# Microphone_Patch_Pedal.net
KiCad netlist of a schematic drawn in EAGLE
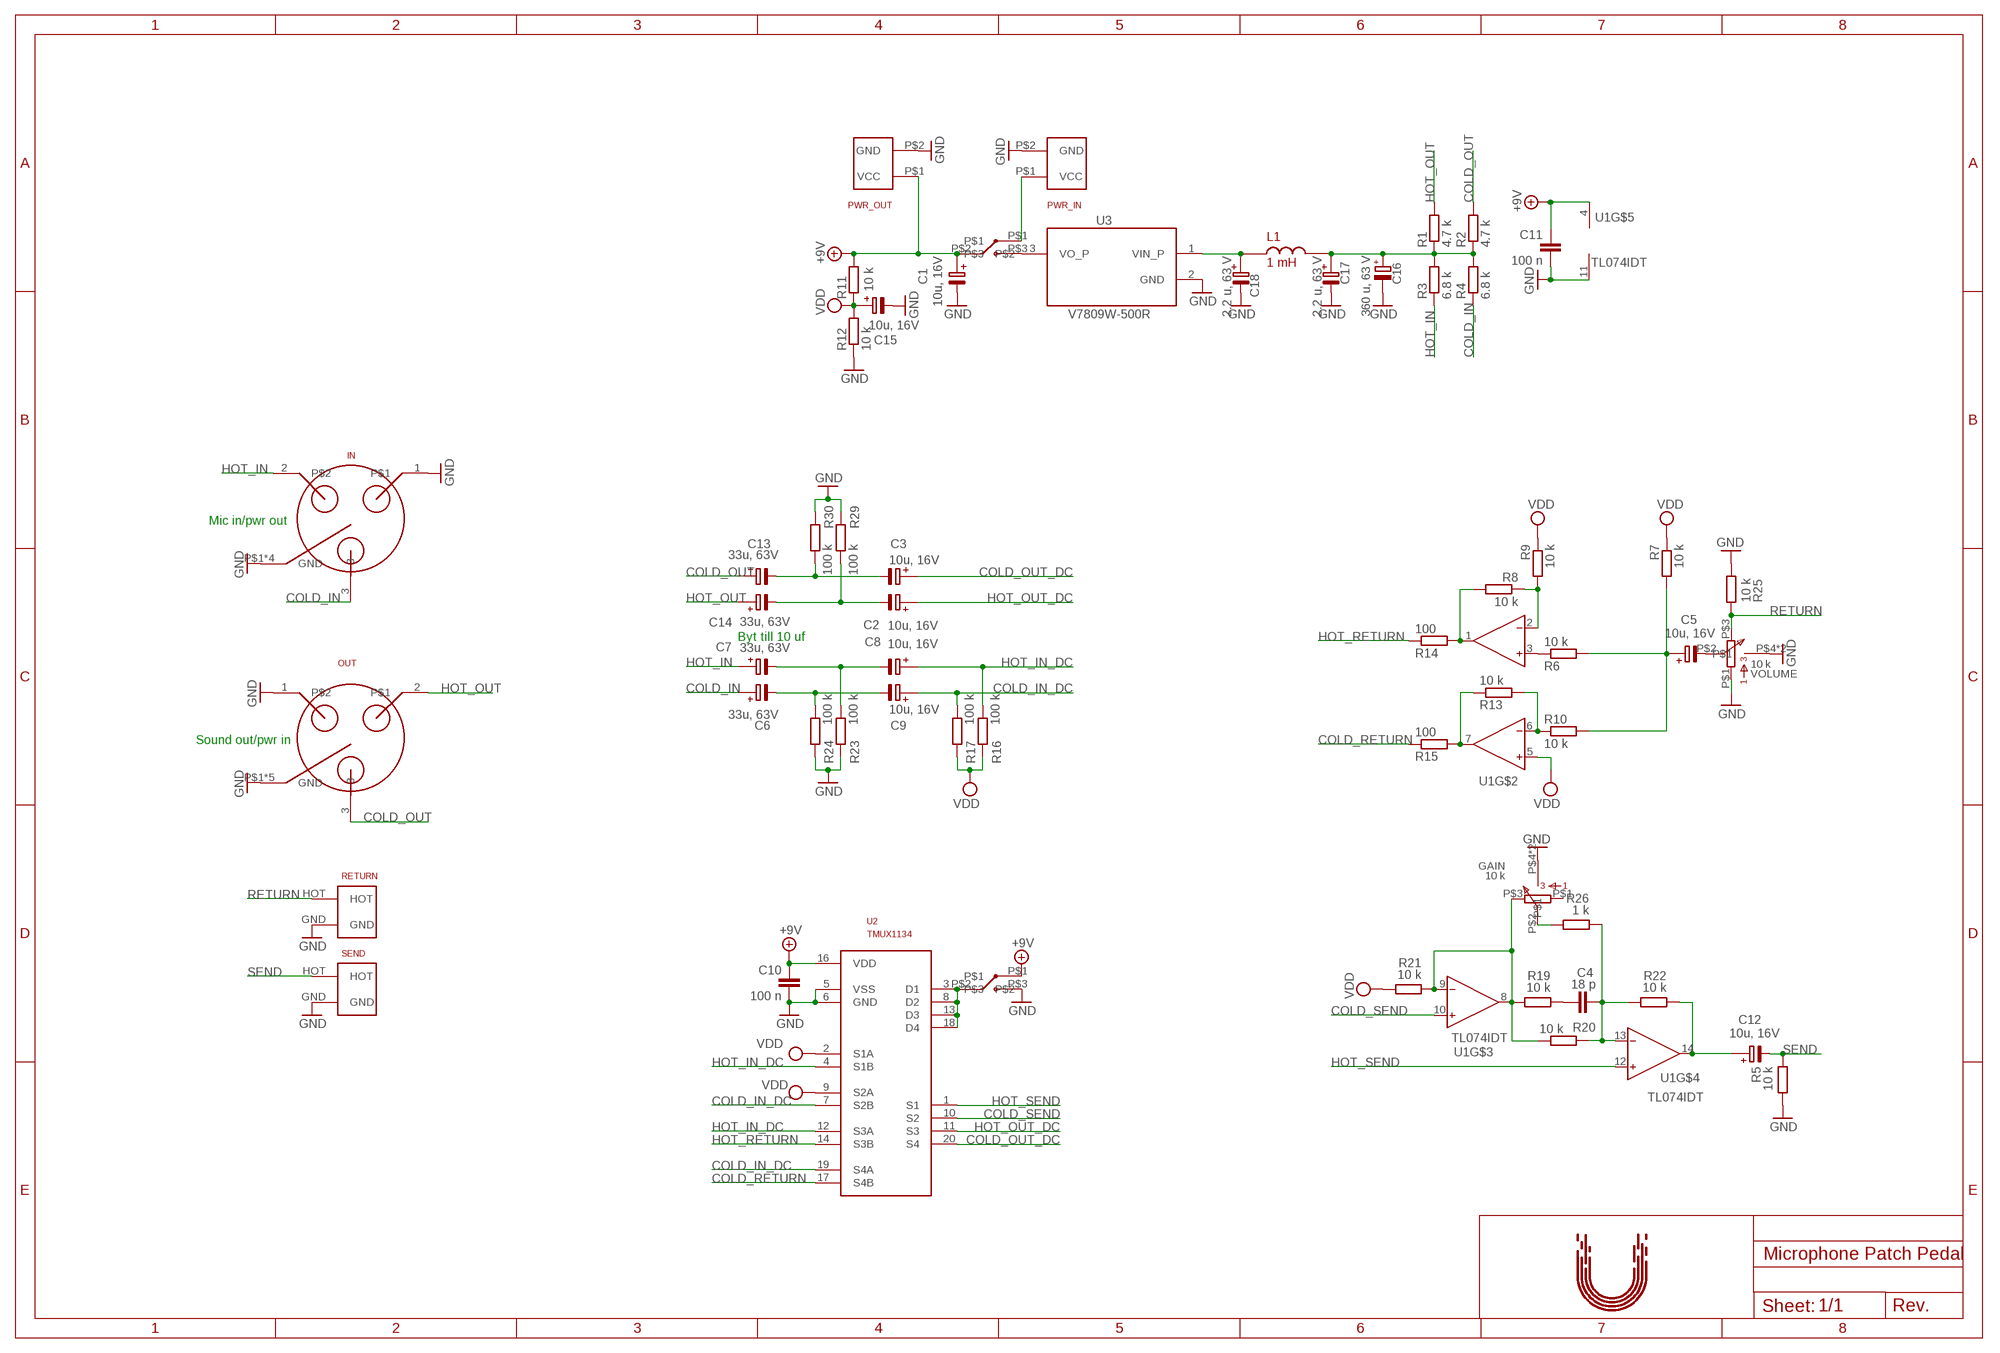
[diagram p0: schematic, sheet 1]

(export (version "E")
  (design (tool "Eeschema 10.0.6"))
  (components
    (comp (ref "BYPASS")
      (value "BUTTON")
      (footprint "eagle-import:3-HOLES")
      (libsource (lib "eagle-import") (part "BUTTON"))
    )
    (comp (ref "C1")
      (value "10u, 16V")
      (footprint "eagle-import:SV-A")
      (fields (field (name "MFR") "Nichicon"))
      (libsource (lib "eagle-import") (part "C-PR-SMD-SV-A"))
    )
    (comp (ref "C2")
      (value "10u, 16V")
      (footprint "eagle-import:SV-A")
      (fields (field (name "MFR") "Nichicon"))
      (libsource (lib "eagle-import") (part "C-PR-SMD-SV-A"))
    )
    (comp (ref "C3")
      (value "10u, 16V")
      (footprint "eagle-import:SV-A")
      (fields (field (name "MFR") "Nichicon"))
      (libsource (lib "eagle-import") (part "C-PR-SMD-SV-A"))
    )
    (comp (ref "C4")
      (value "18 p")
      (footprint "eagle-import:C0603")
      (libsource (lib "eagle-import") (part "C-EUC0603"))
    )
    (comp (ref "C5")
      (value "10u, 16V")
      (footprint "eagle-import:SV-A")
      (fields (field (name "MFR") "Nichicon"))
      (libsource (lib "eagle-import") (part "C-PR-SMD-SV-A"))
    )
    (comp (ref "C6")
      (value "33u, 63V")
      (footprint "eagle-import:SV-E_F")
      (fields (field (name "MFR") "Panasonic"))
      (libsource (lib "eagle-import") (part "C-PR-SMD-SV-E/F"))
    )
    (comp (ref "C7")
      (value "33u, 63V")
      (footprint "eagle-import:SV-E_F")
      (fields (field (name "MFR") "Panasonic"))
      (libsource (lib "eagle-import") (part "C-PR-SMD-SV-E/F"))
    )
    (comp (ref "C8")
      (value "10u, 16V")
      (footprint "eagle-import:SV-A")
      (fields (field (name "MFR") "Nichicon"))
      (libsource (lib "eagle-import") (part "C-PR-SMD-SV-A"))
    )
    (comp (ref "C9")
      (value "10u, 16V")
      (footprint "eagle-import:SV-A")
      (fields (field (name "MFR") "Nichicon"))
      (libsource (lib "eagle-import") (part "C-PR-SMD-SV-A"))
    )
    (comp (ref "C10")
      (value "100 n")
      (footprint "eagle-import:C0603")
      (libsource (lib "eagle-import") (part "C-EUC0603"))
    )
    (comp (ref "C11")
      (value "100 n")
      (footprint "eagle-import:C0603")
      (libsource (lib "eagle-import") (part "C-EUC0603"))
    )
    (comp (ref "C12")
      (value "10u, 16V")
      (footprint "eagle-import:SV-A")
      (fields (field (name "MFR") "Nichicon"))
      (libsource (lib "eagle-import") (part "C-PR-SMD-SV-A"))
    )
    (comp (ref "C13")
      (value "33u, 63V")
      (footprint "eagle-import:SV-E_F")
      (fields (field (name "MFR") "Panasonic"))
      (libsource (lib "eagle-import") (part "C-PR-SMD-SV-E/F"))
    )
    (comp (ref "C14")
      (value "33u, 63V")
      (footprint "eagle-import:SV-E_F")
      (fields (field (name "MFR") "Panasonic"))
      (libsource (lib "eagle-import") (part "C-PR-SMD-SV-E/F"))
    )
    (comp (ref "C15")
      (value "10u, 16V")
      (footprint "eagle-import:SV-A")
      (fields (field (name "MFR") "Nichicon"))
      (libsource (lib "eagle-import") (part "C-PR-SMD-SV-A"))
    )
    (comp (ref "C16")
      (value "360 u, 63 V")
      (footprint "eagle-import:PANASONIC_FK_V_H")
      (fields (field (name "MPN") "UCM1J361MNJ1MS"))
      (libsource (lib "eagle-import") (part "CPOL-EU-PANASONIC_FK_V_H"))
    )
    (comp (ref "C17")
      (value "2.2 u, 63 V")
      (footprint "eagle-import:SV-B")
      (fields (field (name "MPN") "EMVA630ADA2R2MD55G"))
      (libsource (lib "eagle-import") (part "C-PR-SMD-SV-B"))
    )
    (comp (ref "C18")
      (value "2.2 u, 63 V")
      (footprint "eagle-import:SV-B")
      (fields (field (name "MPN") "EMVA630ADA2R2MD55G"))
      (libsource (lib "eagle-import") (part "C-PR-SMD-SV-B"))
    )
    (comp (ref "GAIN")
      (value "10 k")
      (footprint "eagle-import:RK09L1140")
      (libsource (lib "eagle-import") (part "RK09L1140"))
    )
    (comp (ref "IN")
      (value "XLR_FEMALE")
      (footprint "eagle-import:NC3FAH2-S")
      (libsource (lib "eagle-import") (part "XLR_FEMALE"))
    )
    (comp (ref "L1")
      (value "1 mH")
      (footprint "eagle-import:R3225")
      (fields (field (name "MPN") "CBC3225T102KR"))
      (libsource (lib "eagle-import") (part "CBC3225T102KR"))
    )
    (comp (ref "OUT")
      (value "XLR_MALE")
      (footprint "eagle-import:NC3MAH-S")
      (libsource (lib "eagle-import") (part "XLR_MALE"))
    )
    (comp (ref "PWR_IN")
      (value "PWR")
      (footprint "eagle-import:PWR")
      (libsource (lib "eagle-import") (part "PWR"))
    )
    (comp (ref "PWR_OUT")
      (value "PWR")
      (footprint "eagle-import:PWR")
      (libsource (lib "eagle-import") (part "PWR"))
    )
    (comp (ref "R1")
      (value "4.7 k")
      (footprint "eagle-import:R0603")
      (libsource (lib "eagle-import") (part "R-EU_R0603"))
    )
    (comp (ref "R2")
      (value "4.7 k")
      (footprint "eagle-import:R0603")
      (libsource (lib "eagle-import") (part "R-EU_R0603"))
    )
    (comp (ref "R3")
      (value "6.8 k")
      (footprint "eagle-import:R0603")
      (libsource (lib "eagle-import") (part "R-EU_R0603"))
    )
    (comp (ref "R4")
      (value "6.8 k")
      (footprint "eagle-import:R0603")
      (libsource (lib "eagle-import") (part "R-EU_R0603"))
    )
    (comp (ref "R5")
      (value "10 k")
      (footprint "eagle-import:R0603")
      (libsource (lib "eagle-import") (part "R-EU_R0603"))
    )
    (comp (ref "R6")
      (value "10 k")
      (footprint "eagle-import:R0603")
      (libsource (lib "eagle-import") (part "R-EU_R0603"))
    )
    (comp (ref "R7")
      (value "10 k")
      (footprint "eagle-import:R0603")
      (libsource (lib "eagle-import") (part "R-EU_R0603"))
    )
    (comp (ref "R8")
      (value "10 k")
      (footprint "eagle-import:R0603")
      (libsource (lib "eagle-import") (part "R-EU_R0603"))
    )
    (comp (ref "R9")
      (value "10 k")
      (footprint "eagle-import:R0603")
      (libsource (lib "eagle-import") (part "R-EU_R0603"))
    )
    (comp (ref "R10")
      (value "10 k")
      (footprint "eagle-import:R0603")
      (libsource (lib "eagle-import") (part "R-EU_R0603"))
    )
    (comp (ref "R11")
      (value "10 k")
      (footprint "eagle-import:R0603")
      (libsource (lib "eagle-import") (part "R-EU_R0603"))
    )
    (comp (ref "R12")
      (value "10 k")
      (footprint "eagle-import:R0603")
      (libsource (lib "eagle-import") (part "R-EU_R0603"))
    )
    (comp (ref "R13")
      (value "10 k")
      (footprint "eagle-import:R0603")
      (libsource (lib "eagle-import") (part "R-EU_R0603"))
    )
    (comp (ref "R14")
      (value "100")
      (footprint "eagle-import:R0603")
      (libsource (lib "eagle-import") (part "R-EU_R0603"))
    )
    (comp (ref "R15")
      (value "100")
      (footprint "eagle-import:R0603")
      (libsource (lib "eagle-import") (part "R-EU_R0603"))
    )
    (comp (ref "R16")
      (value "100 k")
      (footprint "eagle-import:R0603")
      (libsource (lib "eagle-import") (part "R-EU_R0603"))
    )
    (comp (ref "R17")
      (value "100 k")
      (footprint "eagle-import:R0603")
      (libsource (lib "eagle-import") (part "R-EU_R0603"))
    )
    (comp (ref "R19")
      (value "10 k")
      (footprint "eagle-import:R0603")
      (libsource (lib "eagle-import") (part "R-EU_R0603"))
    )
    (comp (ref "R20")
      (value "10 k")
      (footprint "eagle-import:R0603")
      (libsource (lib "eagle-import") (part "R-EU_R0603"))
    )
    (comp (ref "R21")
      (value "10 k")
      (footprint "eagle-import:R0603")
      (libsource (lib "eagle-import") (part "R-EU_R0603"))
    )
    (comp (ref "R22")
      (value "10 k")
      (footprint "eagle-import:R0603")
      (libsource (lib "eagle-import") (part "R-EU_R0603"))
    )
    (comp (ref "R23")
      (value "100 k")
      (footprint "eagle-import:R0603")
      (libsource (lib "eagle-import") (part "R-EU_R0603"))
    )
    (comp (ref "R24")
      (value "100 k")
      (footprint "eagle-import:R0603")
      (libsource (lib "eagle-import") (part "R-EU_R0603"))
    )
    (comp (ref "R25")
      (value "10 k")
      (footprint "eagle-import:R0603")
      (libsource (lib "eagle-import") (part "R-EU_R0603"))
    )
    (comp (ref "R26")
      (value "1 k")
      (footprint "eagle-import:R0603")
      (libsource (lib "eagle-import") (part "R-EU_R0603"))
    )
    (comp (ref "R29")
      (value "100 k")
      (footprint "eagle-import:R0603")
      (libsource (lib "eagle-import") (part "R-EU_R0603"))
    )
    (comp (ref "R30")
      (value "100 k")
      (footprint "eagle-import:R0603")
      (libsource (lib "eagle-import") (part "R-EU_R0603"))
    )
    (comp (ref "RETURN")
      (value "UNBALANCED_INPUT_JACK")
      (footprint "eagle-import:BALANCED_INPUT_JACK")
      (libsource (lib "eagle-import") (part "UNBALANCED_INPUT_JACK"))
    )
    (comp (ref "SEND")
      (value "UNBALANCED_INPUT_JACK")
      (footprint "eagle-import:BALANCED_INPUT_JACK")
      (libsource (lib "eagle-import") (part "UNBALANCED_INPUT_JACK"))
    )
    (comp (ref "SWITCH")
      (value "BUTTON")
      (footprint "eagle-import:3-HOLES")
      (libsource (lib "eagle-import") (part "BUTTON"))
    )
    (comp (ref "U$1")
      (value "UTBULT_DESIGN4")
      (footprint "eagle-import:UD_4")
      (libsource (lib "eagle-import") (part "UTBULT_DESIGN4"))
    )
    (comp (ref "U1")
      (value "TL074IDT")
      (footprint "eagle-import:SOIC127P600X175-14N")
      (fields (field (name "MFR") "STMicroelectronics"))
      (libsource (lib "eagle-import") (part "TL074IDT"))
    )
    (comp (ref "U2")
      (value "TMUX1134")
      (footprint "eagle-import:SOP65P640X120-20N")
      (fields (field (name "MPN") "TMUX1134PWR "))
      (libsource (lib "eagle-import") (part "TMUX1134"))
    )
    (comp (ref "U3")
      (value "V7809W-500R")
      (footprint "eagle-import:CONV_V7809W-500R")
      (libsource (lib "eagle-import") (part "V7809W-500R"))
    )
    (comp (ref "VOLUME")
      (value "10 k")
      (footprint "eagle-import:RK09L1140")
      (libsource (lib "eagle-import") (part "RK09L1140"))
    )
  )
  (nets
    (net (code "1") (name "+9V") (class "Default")
      (node (ref "BYPASS") (pin "P$1") (pinfunction "P$1_P$1") (pintype "bidirectional"))
      (node (ref "C1") (pin "+") (pinfunction "+_+") (pintype "passive"))
      (node (ref "C10") (pin "1") (pinfunction "1_1") (pintype "passive"))
      (node (ref "C11") (pin "1") (pinfunction "1_1") (pintype "passive"))
      (node (ref "PWR_OUT") (pin "P$1") (pinfunction "VCC_P$1") (pintype "bidirectional"))
      (node (ref "R11") (pin "2") (pinfunction "2_2") (pintype "passive"))
      (node (ref "SWITCH") (pin "P$2") (pinfunction "P$2_P$2") (pintype "bidirectional"))
      (node (ref "U1") (pin "4") (pinfunction "V+_4") (pintype "power_in"))
      (node (ref "U2") (pin "16") (pinfunction "VDD_16") (pintype "bidirectional"))
    )
    (net (code "2") (name "/COLD_IN") (class "Default")
      (node (ref "C6") (pin "+") (pinfunction "+_+") (pintype "passive"))
      (node (ref "IN") (pin "3") (pinfunction "3_3") (pintype "bidirectional"))
      (node (ref "R4") (pin "1") (pinfunction "1_1") (pintype "passive"))
    )
    (net (code "3") (name "/COLD_IN_DC") (class "Default")
      (node (ref "C9") (pin "+") (pinfunction "+_+") (pintype "passive"))
      (node (ref "R17") (pin "2") (pinfunction "2_2") (pintype "passive"))
      (node (ref "U2") (pin "19") (pinfunction "S4A_19") (pintype "bidirectional"))
      (node (ref "U2") (pin "7") (pinfunction "S2B_7") (pintype "bidirectional"))
    )
    (net (code "4") (name "/COLD_OUT") (class "Default")
      (node (ref "C13") (pin "+") (pinfunction "+_+") (pintype "passive"))
      (node (ref "OUT") (pin "3") (pinfunction "3_3") (pintype "bidirectional"))
      (node (ref "R2") (pin "2") (pinfunction "2_2") (pintype "passive"))
    )
    (net (code "5") (name "/COLD_OUT_DC") (class "Default")
      (node (ref "C3") (pin "+") (pinfunction "+_+") (pintype "passive"))
      (node (ref "U2") (pin "20") (pinfunction "S4_20") (pintype "bidirectional"))
    )
    (net (code "6") (name "/COLD_RETURN") (class "Default")
      (node (ref "R15") (pin "1") (pinfunction "1_1") (pintype "passive"))
      (node (ref "U2") (pin "17") (pinfunction "S4B_17") (pintype "bidirectional"))
    )
    (net (code "7") (name "/COLD_SEND") (class "Default")
      (node (ref "U1") (pin "10") (pinfunction "IN+_10") (pintype "input"))
      (node (ref "U2") (pin "10") (pinfunction "S2_10") (pintype "bidirectional"))
    )
    (net (code "8") (name "/HOT_IN") (class "Default")
      (node (ref "C7") (pin "+") (pinfunction "+_+") (pintype "passive"))
      (node (ref "IN") (pin "2") (pinfunction "P$2_2") (pintype "bidirectional"))
      (node (ref "R3") (pin "1") (pinfunction "1_1") (pintype "passive"))
    )
    (net (code "9") (name "/HOT_IN_DC") (class "Default")
      (node (ref "C8") (pin "+") (pinfunction "+_+") (pintype "passive"))
      (node (ref "R16") (pin "2") (pinfunction "2_2") (pintype "passive"))
      (node (ref "U2") (pin "12") (pinfunction "S3A_12") (pintype "bidirectional"))
      (node (ref "U2") (pin "4") (pinfunction "S1B_4") (pintype "bidirectional"))
    )
    (net (code "10") (name "/HOT_OUT") (class "Default")
      (node (ref "C14") (pin "+") (pinfunction "+_+") (pintype "passive"))
      (node (ref "OUT") (pin "2") (pinfunction "P$1_2") (pintype "bidirectional"))
      (node (ref "R1") (pin "2") (pinfunction "2_2") (pintype "passive"))
    )
    (net (code "11") (name "/HOT_OUT_DC") (class "Default")
      (node (ref "C2") (pin "+") (pinfunction "+_+") (pintype "passive"))
      (node (ref "U2") (pin "11") (pinfunction "S3_11") (pintype "bidirectional"))
    )
    (net (code "12") (name "/HOT_RETURN") (class "Default")
      (node (ref "R14") (pin "1") (pinfunction "1_1") (pintype "passive"))
      (node (ref "U2") (pin "14") (pinfunction "S3B_14") (pintype "bidirectional"))
    )
    (net (code "13") (name "/HOT_SEND") (class "Default")
      (node (ref "U1") (pin "12") (pinfunction "IN+_12") (pintype "input"))
      (node (ref "U2") (pin "1") (pinfunction "S1_1") (pintype "bidirectional"))
    )
    (net (code "14") (name "/RETURN") (class "Default")
      (node (ref "R25") (pin "1") (pinfunction "1_1") (pintype "passive"))
      (node (ref "RETURN") (pin "HOT") (pinfunction "HOT_HOT") (pintype "bidirectional"))
      (node (ref "VOLUME") (pin "P$3") (pinfunction "3_P$3") (pintype "passive"))
    )
    (net (code "15") (name "/SEND") (class "Default")
      (node (ref "C12") (pin "-") (pinfunction "-_-") (pintype "passive"))
      (node (ref "R5") (pin "1") (pinfunction "1_1") (pintype "passive"))
      (node (ref "SEND") (pin "HOT") (pinfunction "HOT_HOT") (pintype "bidirectional"))
    )
    (net (code "16") (name "GND") (class "Default")
      (node (ref "BYPASS") (pin "P$3") (pinfunction "P$3_P$3") (pintype "bidirectional"))
      (node (ref "C1") (pin "-") (pinfunction "-_-") (pintype "passive"))
      (node (ref "C10") (pin "2") (pinfunction "2_2") (pintype "passive"))
      (node (ref "C11") (pin "2") (pinfunction "2_2") (pintype "passive"))
      (node (ref "C15") (pin "-") (pinfunction "-_-") (pintype "passive"))
      (node (ref "C16") (pin "-") (pinfunction "-_-") (pintype "passive"))
      (node (ref "C17") (pin "-") (pinfunction "-_-") (pintype "passive"))
      (node (ref "C18") (pin "-") (pinfunction "-_-") (pintype "passive"))
      (node (ref "GAIN") (pin "P$4") (pinfunction "P$1_P$4") (pintype "bidirectional"))
      (node (ref "GAIN") (pin "P$5") (pinfunction "P$1_P$5") (pintype "bidirectional"))
      (node (ref "IN") (pin "1") (pinfunction "P$1_1") (pintype "bidirectional"))
      (node (ref "IN") (pin "P$1") (pinfunction "GND_P$1") (pintype "bidirectional"))
      (node (ref "IN") (pin "P$2") (pinfunction "GND_P$2") (pintype "bidirectional"))
      (node (ref "IN") (pin "P$3") (pinfunction "GND_P$3") (pintype "bidirectional"))
      (node (ref "IN") (pin "P$6") (pinfunction "GND_P$6") (pintype "bidirectional"))
      (node (ref "OUT") (pin "1") (pinfunction "P$2_1") (pintype "bidirectional"))
      (node (ref "OUT") (pin "P$1") (pinfunction "GND_P$1") (pintype "bidirectional"))
      (node (ref "OUT") (pin "P$2") (pinfunction "GND_P$2") (pintype "bidirectional"))
      (node (ref "OUT") (pin "P$3") (pinfunction "GND_P$3") (pintype "bidirectional"))
      (node (ref "OUT") (pin "P$4") (pinfunction "GND_P$4") (pintype "bidirectional"))
      (node (ref "OUT") (pin "P$5") (pinfunction "GND_P$5") (pintype "bidirectional"))
      (node (ref "PWR_IN") (pin "P$2") (pinfunction "GND_P$2") (pintype "bidirectional"))
      (node (ref "PWR_OUT") (pin "P$2") (pinfunction "GND_P$2") (pintype "bidirectional"))
      (node (ref "R12") (pin "1") (pinfunction "1_1") (pintype "passive"))
      (node (ref "R23") (pin "1") (pinfunction "1_1") (pintype "passive"))
      (node (ref "R24") (pin "1") (pinfunction "1_1") (pintype "passive"))
      (node (ref "R25") (pin "2") (pinfunction "2_2") (pintype "passive"))
      (node (ref "R29") (pin "1") (pinfunction "1_1") (pintype "passive"))
      (node (ref "R30") (pin "1") (pinfunction "1_1") (pintype "passive"))
      (node (ref "R5") (pin "2") (pinfunction "2_2") (pintype "passive"))
      (node (ref "RETURN") (pin "GND") (pinfunction "GND_GND") (pintype "bidirectional"))
      (node (ref "SEND") (pin "GND") (pinfunction "GND_GND") (pintype "bidirectional"))
      (node (ref "U1") (pin "11") (pinfunction "V-_11") (pintype "power_in"))
      (node (ref "U2") (pin "5") (pinfunction "VSS_5") (pintype "bidirectional"))
      (node (ref "U2") (pin "6") (pinfunction "GND_6") (pintype "bidirectional"))
      (node (ref "U3") (pin "2") (pinfunction "GND_2") (pintype "power_in"))
      (node (ref "VOLUME") (pin "P$1") (pinfunction "1_P$1") (pintype "passive"))
      (node (ref "VOLUME") (pin "P$4") (pinfunction "P$1_P$4") (pintype "bidirectional"))
      (node (ref "VOLUME") (pin "P$5") (pinfunction "P$1_P$5") (pintype "bidirectional"))
    )
    (net (code "17") (name "Net-(C4-Pad1)") (class "Default")
      (node (ref "C4") (pin "1") (pinfunction "1_1") (pintype "passive"))
      (node (ref "R19") (pin "1") (pinfunction "1_1") (pintype "passive"))
    )
    (net (code "18") (name "Net-(C5-Pad+)") (class "Default")
      (node (ref "C5") (pin "+") (pinfunction "+_+") (pintype "passive"))
      (node (ref "R10") (pin "2") (pinfunction "2_2") (pintype "passive"))
      (node (ref "R6") (pin "2") (pinfunction "2_2") (pintype "passive"))
      (node (ref "R7") (pin "2") (pinfunction "2_2") (pintype "passive"))
    )
    (net (code "19") (name "Net-(C6-Pad-)") (class "Default")
      (node (ref "C6") (pin "-") (pinfunction "-_-") (pintype "passive"))
      (node (ref "C9") (pin "-") (pinfunction "-_-") (pintype "passive"))
      (node (ref "R24") (pin "2") (pinfunction "2_2") (pintype "passive"))
    )
    (net (code "20") (name "Net-(C7-Pad-)") (class "Default")
      (node (ref "C7") (pin "-") (pinfunction "-_-") (pintype "passive"))
      (node (ref "C8") (pin "-") (pinfunction "-_-") (pintype "passive"))
      (node (ref "R23") (pin "2") (pinfunction "2_2") (pintype "passive"))
    )
    (net (code "21") (name "Net-(C13-Pad-)") (class "Default")
      (node (ref "C13") (pin "-") (pinfunction "-_-") (pintype "passive"))
      (node (ref "C3") (pin "-") (pinfunction "-_-") (pintype "passive"))
      (node (ref "R30") (pin "2") (pinfunction "2_2") (pintype "passive"))
    )
    (net (code "22") (name "Net-(C14-Pad-)") (class "Default")
      (node (ref "C14") (pin "-") (pinfunction "-_-") (pintype "passive"))
      (node (ref "C2") (pin "-") (pinfunction "-_-") (pintype "passive"))
      (node (ref "R29") (pin "2") (pinfunction "2_2") (pintype "passive"))
    )
    (net (code "23") (name "Net-(GAIN-2)") (class "Default")
      (node (ref "GAIN") (pin "P$2") (pinfunction "2_P$2") (pintype "passive"))
      (node (ref "R26") (pin "2") (pinfunction "2_2") (pintype "passive"))
    )
    (net (code "24") (name "Net-(GAIN-3)") (class "Default")
      (node (ref "GAIN") (pin "P$3") (pinfunction "3_P$3") (pintype "passive"))
      (node (ref "R19") (pin "2") (pinfunction "2_2") (pintype "passive"))
      (node (ref "R20") (pin "2") (pinfunction "2_2") (pintype "passive"))
      (node (ref "R21") (pin "1") (pinfunction "1_1") (pintype "passive"))
      (node (ref "U1") (pin "8") (pinfunction "OUT_8") (pintype "output"))
      (node (ref "U1") (pin "9") (pinfunction "IN-_9") (pintype "input"))
    )
    (net (code "25") (name "Net-(L1-P$1)") (class "Default")
      (node (ref "C18") (pin "+") (pinfunction "+_+") (pintype "passive"))
      (node (ref "L1") (pin "1") (pinfunction "P$1_1") (pintype "bidirectional"))
      (node (ref "U3") (pin "1") (pinfunction "VIN_P_1") (pintype "input"))
    )
    (net (code "26") (name "Net-(L1-P$2)") (class "Default")
      (node (ref "C16") (pin "+") (pinfunction "+_+") (pintype "passive"))
      (node (ref "C17") (pin "+") (pinfunction "+_+") (pintype "passive"))
      (node (ref "L1") (pin "2") (pinfunction "P$2_2") (pintype "bidirectional"))
      (node (ref "R1") (pin "1") (pinfunction "1_1") (pintype "passive"))
      (node (ref "R2") (pin "1") (pinfunction "1_1") (pintype "passive"))
      (node (ref "R3") (pin "2") (pinfunction "2_2") (pintype "passive"))
      (node (ref "R4") (pin "2") (pinfunction "2_2") (pintype "passive"))
    )
    (net (code "27") (name "Net-(PWR_IN-VCC)") (class "Default")
      (node (ref "PWR_IN") (pin "P$1") (pinfunction "VCC_P$1") (pintype "bidirectional"))
      (node (ref "SWITCH") (pin "P$1") (pinfunction "P$1_P$1") (pintype "bidirectional"))
    )
    (net (code "28") (name "Net-(U1A-IN+)") (class "Default")
      (node (ref "R6") (pin "1") (pinfunction "1_1") (pintype "passive"))
      (node (ref "U1") (pin "3") (pinfunction "IN+_3") (pintype "input"))
    )
    (net (code "29") (name "Net-(U1A-IN-)") (class "Default")
      (node (ref "R8") (pin "1") (pinfunction "1_1") (pintype "passive"))
      (node (ref "R9") (pin "2") (pinfunction "2_2") (pintype "passive"))
      (node (ref "U1") (pin "2") (pinfunction "IN-_2") (pintype "input"))
    )
    (net (code "30") (name "Net-(U1A-OUT)") (class "Default")
      (node (ref "R14") (pin "2") (pinfunction "2_2") (pintype "passive"))
      (node (ref "R8") (pin "2") (pinfunction "2_2") (pintype "passive"))
      (node (ref "U1") (pin "1") (pinfunction "OUT_1") (pintype "output"))
    )
    (net (code "31") (name "Net-(U1B-IN-)") (class "Default")
      (node (ref "R10") (pin "1") (pinfunction "1_1") (pintype "passive"))
      (node (ref "R13") (pin "2") (pinfunction "2_2") (pintype "passive"))
      (node (ref "U1") (pin "6") (pinfunction "IN-_6") (pintype "input"))
    )
    (net (code "32") (name "Net-(U1B-OUT)") (class "Default")
      (node (ref "R13") (pin "1") (pinfunction "1_1") (pintype "passive"))
      (node (ref "R15") (pin "2") (pinfunction "2_2") (pintype "passive"))
      (node (ref "U1") (pin "7") (pinfunction "OUT_7") (pintype "output"))
    )
    (net (code "33") (name "Net-(U1D-IN-)") (class "Default")
      (node (ref "C4") (pin "2") (pinfunction "2_2") (pintype "passive"))
      (node (ref "R20") (pin "1") (pinfunction "1_1") (pintype "passive"))
      (node (ref "R22") (pin "2") (pinfunction "2_2") (pintype "passive"))
      (node (ref "R26") (pin "1") (pinfunction "1_1") (pintype "passive"))
      (node (ref "U1") (pin "13") (pinfunction "IN-_13") (pintype "input"))
    )
    (net (code "34") (name "Net-(U1D-OUT)") (class "Default")
      (node (ref "C12") (pin "+") (pinfunction "+_+") (pintype "passive"))
      (node (ref "R22") (pin "1") (pinfunction "1_1") (pintype "passive"))
      (node (ref "U1") (pin "14") (pinfunction "OUT_14") (pintype "output"))
    )
    (net (code "35") (name "Net-(U2-D1)") (class "Default")
      (node (ref "BYPASS") (pin "P$2") (pinfunction "P$2_P$2") (pintype "bidirectional"))
      (node (ref "U2") (pin "13") (pinfunction "D3_13") (pintype "bidirectional"))
      (node (ref "U2") (pin "18") (pinfunction "D4_18") (pintype "bidirectional"))
      (node (ref "U2") (pin "3") (pinfunction "D1_3") (pintype "bidirectional"))
      (node (ref "U2") (pin "8") (pinfunction "D2_8") (pintype "bidirectional"))
    )
    (net (code "36") (name "Net-(U3-VO_P)") (class "Default")
      (node (ref "SWITCH") (pin "P$3") (pinfunction "P$3_P$3") (pintype "bidirectional"))
      (node (ref "U3") (pin "3") (pinfunction "VO_P_3") (pintype "output"))
    )
    (net (code "37") (name "Net-(VOLUME-2)") (class "Default")
      (node (ref "C5") (pin "-") (pinfunction "-_-") (pintype "passive"))
      (node (ref "VOLUME") (pin "P$2") (pinfunction "2_P$2") (pintype "passive"))
    )
    (net (code "38") (name "VDD") (class "Default")
      (node (ref "C15") (pin "+") (pinfunction "+_+") (pintype "passive"))
      (node (ref "R11") (pin "1") (pinfunction "1_1") (pintype "passive"))
      (node (ref "R12") (pin "2") (pinfunction "2_2") (pintype "passive"))
      (node (ref "R16") (pin "1") (pinfunction "1_1") (pintype "passive"))
      (node (ref "R17") (pin "1") (pinfunction "1_1") (pintype "passive"))
      (node (ref "R21") (pin "2") (pinfunction "2_2") (pintype "passive"))
      (node (ref "R7") (pin "1") (pinfunction "1_1") (pintype "passive"))
      (node (ref "R9") (pin "1") (pinfunction "1_1") (pintype "passive"))
      (node (ref "U1") (pin "5") (pinfunction "IN+_5") (pintype "input"))
      (node (ref "U2") (pin "2") (pinfunction "S1A_2") (pintype "bidirectional"))
      (node (ref "U2") (pin "9") (pinfunction "S2A_9") (pintype "bidirectional"))
    )
    (net (code "39") (name "unconnected-(GAIN-1-PadP$1)") (class "Default")
      (node (ref "GAIN") (pin "P$1") (pinfunction "1_P$1") (pintype "passive"))
    )
  )
)
